# FPGA_Banks_DDR3.net
KiCad netlist of a schematic drawn in Altium Designer
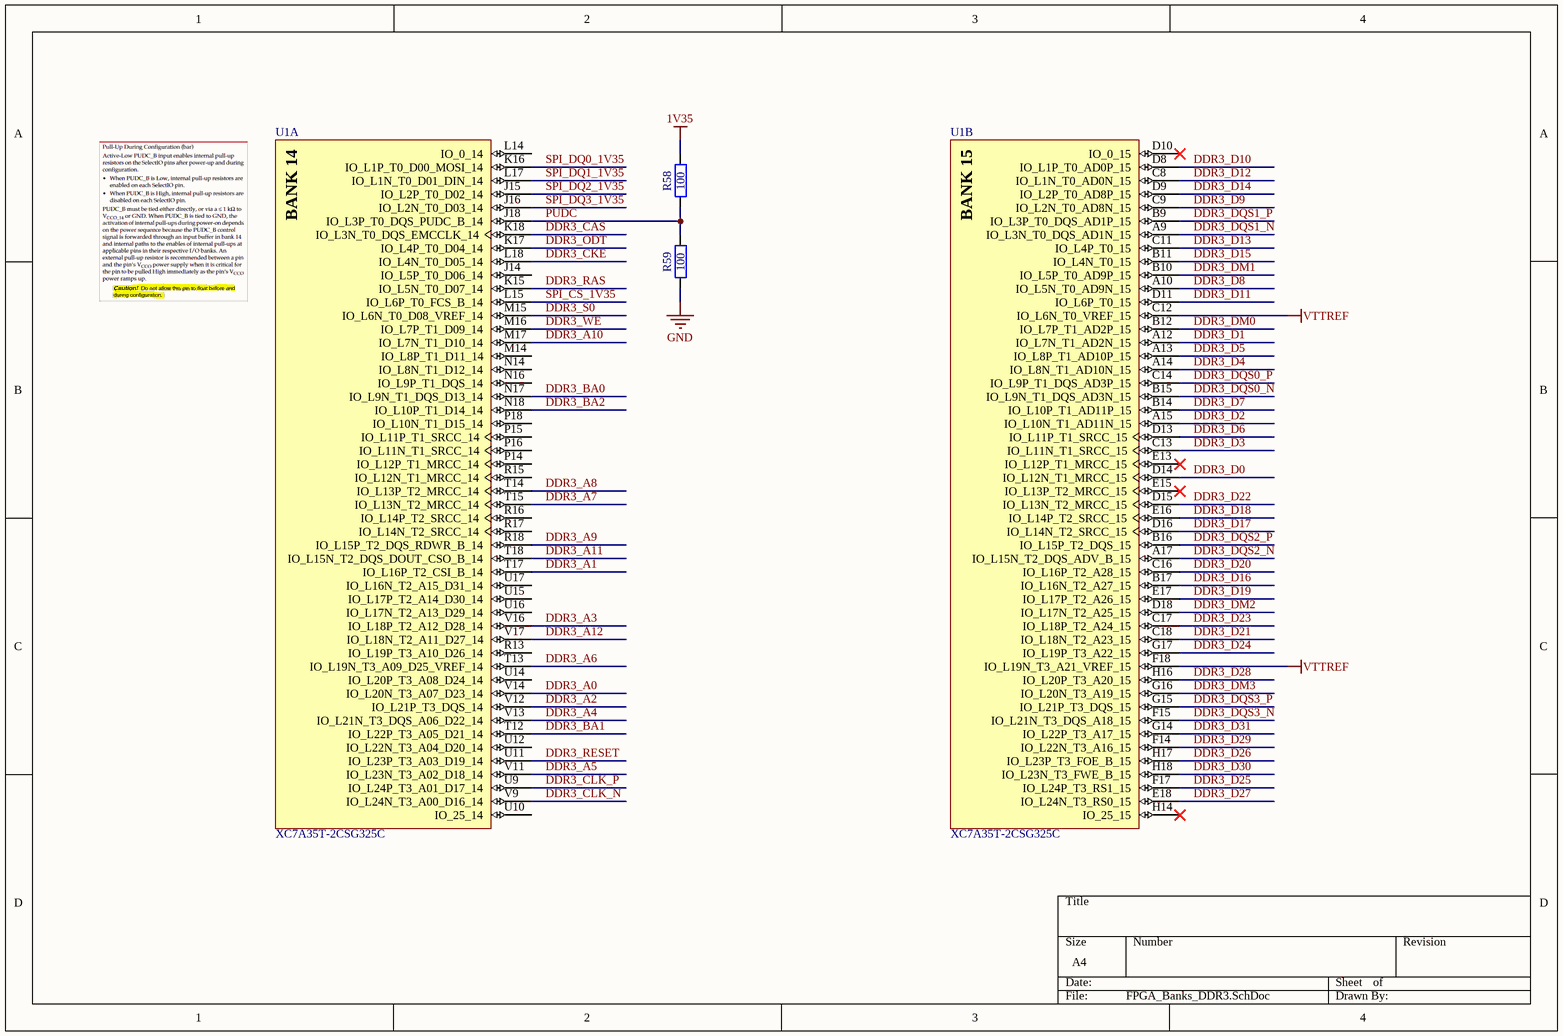
[diagram p0: FPGA_Banks_DDR3.SchDoc]

(export (version "E")
  (design (tool "Eeschema 10.0.6"))
  (components
    (comp (ref "R58")
      (value "100")
      (footprint "GEN_R_0201")
      (fields (field (name "TOLERANCE") "1%"))
      (libsource (lib "DSO") (part "RES 100 OHM 1% 1/20W 0201"))
    )
    (comp (ref "R59")
      (value "100")
      (footprint "GEN_R_0201")
      (fields (field (name "TOLERANCE") "1%"))
      (libsource (lib "DSO") (part "RES 100 OHM 1% 1/20W 0201"))
    )
    (comp (ref "U1")
      (value "XC7A35T-2CSG325C")
      (footprint "CSG325")
      (description "Artix-7 FPGA, 150 User I/Os, 4 GTP, 324-Ball BGA, Speed Grade 2, Commercial Grade, Pb-Free")
      (fields (field (name "MANUFACTURER") "Xilinx"))
      (libsource (lib "Xilinx Artix-7") (part "XC7A35T-2CSG325C"))
    )
  )
  (nets
    (net (code "1") (name "/DDR3_A0") (class "Default")
      (node (ref "U1") (pin "V14") (pinfunction "IO_L20N_T3_A07_D23_14_V14") (pintype "bidirectional"))
    )
    (net (code "2") (name "/DDR3_A1") (class "Default")
      (node (ref "U1") (pin "T17") (pinfunction "IO_L16P_T2_CSI_B_14_T17") (pintype "bidirectional"))
    )
    (net (code "3") (name "/DDR3_A2") (class "Default")
      (node (ref "U1") (pin "V12") (pinfunction "IO_L21P_T3_DQS_14_V12") (pintype "bidirectional"))
    )
    (net (code "4") (name "/DDR3_A3") (class "Default")
      (node (ref "U1") (pin "V16") (pinfunction "IO_L18P_T2_A12_D28_14_V16") (pintype "bidirectional"))
    )
    (net (code "5") (name "/DDR3_A4") (class "Default")
      (node (ref "U1") (pin "V13") (pinfunction "IO_L21N_T3_DQS_A06_D22_14_V13") (pintype "bidirectional"))
    )
    (net (code "6") (name "/DDR3_A5") (class "Default")
      (node (ref "U1") (pin "V11") (pinfunction "IO_L23N_T3_A02_D18_14_V11") (pintype "bidirectional"))
    )
    (net (code "7") (name "/DDR3_A6") (class "Default")
      (node (ref "U1") (pin "T13") (pinfunction "IO_L19N_T3_A09_D25_VREF_14_T13") (pintype "bidirectional"))
    )
    (net (code "8") (name "/DDR3_A7") (class "Default")
      (node (ref "U1") (pin "T15") (pinfunction "IO_L13N_T2_MRCC_14_T15") (pintype "bidirectional"))
    )
    (net (code "9") (name "/DDR3_A8") (class "Default")
      (node (ref "U1") (pin "T14") (pinfunction "IO_L13P_T2_MRCC_14_T14") (pintype "bidirectional"))
    )
    (net (code "10") (name "/DDR3_A9") (class "Default")
      (node (ref "U1") (pin "R18") (pinfunction "IO_L15P_T2_DQS_RDWR_B_14_R18") (pintype "bidirectional"))
    )
    (net (code "11") (name "/DDR3_A10") (class "Default")
      (node (ref "U1") (pin "M17") (pinfunction "IO_L7N_T1_D10_14_M17") (pintype "bidirectional"))
    )
    (net (code "12") (name "/DDR3_A11") (class "Default")
      (node (ref "U1") (pin "T18") (pinfunction "IO_L15N_T2_DQS_DOUT_CSO_B_14_T18") (pintype "bidirectional"))
    )
    (net (code "13") (name "/DDR3_A12") (class "Default")
      (node (ref "U1") (pin "V17") (pinfunction "IO_L18N_T2_A11_D27_14_V17") (pintype "bidirectional"))
    )
    (net (code "14") (name "/DDR3_BA0") (class "Default")
      (node (ref "U1") (pin "N17") (pinfunction "IO_L9N_T1_DQS_D13_14_N17") (pintype "bidirectional"))
    )
    (net (code "15") (name "/DDR3_BA1") (class "Default")
      (node (ref "U1") (pin "T12") (pinfunction "IO_L22P_T3_A05_D21_14_T12") (pintype "bidirectional"))
    )
    (net (code "16") (name "/DDR3_BA2") (class "Default")
      (node (ref "U1") (pin "N18") (pinfunction "IO_L10P_T1_D14_14_N18") (pintype "bidirectional"))
    )
    (net (code "17") (name "/DDR3_CAS") (class "Default")
      (node (ref "U1") (pin "K18") (pinfunction "IO_L3N_T0_DQS_EMCCLK_14_K18") (pintype "bidirectional"))
    )
    (net (code "18") (name "/DDR3_CKE") (class "Default")
      (node (ref "U1") (pin "L18") (pinfunction "IO_L4N_T0_D05_14_L18") (pintype "bidirectional"))
    )
    (net (code "19") (name "/DDR3_CLK_N") (class "Default")
      (node (ref "U1") (pin "V9") (pinfunction "IO_L24N_T3_A00_D16_14_V9") (pintype "bidirectional"))
    )
    (net (code "20") (name "/DDR3_CLK_P") (class "Default")
      (node (ref "U1") (pin "U9") (pinfunction "IO_L24P_T3_A01_D17_14_U9") (pintype "bidirectional"))
    )
    (net (code "21") (name "/DDR3_D0") (class "Default")
      (node (ref "U1") (pin "D14") (pinfunction "IO_L12N_T1_MRCC_15_D14") (pintype "bidirectional"))
    )
    (net (code "22") (name "/DDR3_D1") (class "Default")
      (node (ref "U1") (pin "A12") (pinfunction "IO_L7N_T1_AD2N_15_A12") (pintype "bidirectional"))
    )
    (net (code "23") (name "/DDR3_D2") (class "Default")
      (node (ref "U1") (pin "A15") (pinfunction "IO_L10N_T1_AD11N_15_A15") (pintype "bidirectional"))
    )
    (net (code "24") (name "/DDR3_D3") (class "Default")
      (node (ref "U1") (pin "C13") (pinfunction "IO_L11N_T1_SRCC_15_C13") (pintype "bidirectional"))
    )
    (net (code "25") (name "/DDR3_D4") (class "Default")
      (node (ref "U1") (pin "A14") (pinfunction "IO_L8N_T1_AD10N_15_A14") (pintype "bidirectional"))
    )
    (net (code "26") (name "/DDR3_D5") (class "Default")
      (node (ref "U1") (pin "A13") (pinfunction "IO_L8P_T1_AD10P_15_A13") (pintype "bidirectional"))
    )
    (net (code "27") (name "/DDR3_D6") (class "Default")
      (node (ref "U1") (pin "D13") (pinfunction "IO_L11P_T1_SRCC_15_D13") (pintype "bidirectional"))
    )
    (net (code "28") (name "/DDR3_D7") (class "Default")
      (node (ref "U1") (pin "B14") (pinfunction "IO_L10P_T1_AD11P_15_B14") (pintype "bidirectional"))
    )
    (net (code "29") (name "/DDR3_D8") (class "Default")
      (node (ref "U1") (pin "A10") (pinfunction "IO_L5N_T0_AD9N_15_A10") (pintype "bidirectional"))
    )
    (net (code "30") (name "/DDR3_D9") (class "Default")
      (node (ref "U1") (pin "C9") (pinfunction "IO_L2N_T0_AD8N_15_C9") (pintype "bidirectional"))
    )
    (net (code "31") (name "/DDR3_D10") (class "Default")
      (node (ref "U1") (pin "D8") (pinfunction "IO_L1P_T0_AD0P_15_D8") (pintype "bidirectional"))
    )
    (net (code "32") (name "/DDR3_D11") (class "Default")
      (node (ref "U1") (pin "D11") (pinfunction "IO_L6P_T0_15_D11") (pintype "bidirectional"))
    )
    (net (code "33") (name "/DDR3_D12") (class "Default")
      (node (ref "U1") (pin "C8") (pinfunction "IO_L1N_T0_AD0N_15_C8") (pintype "bidirectional"))
    )
    (net (code "34") (name "/DDR3_D13") (class "Default")
      (node (ref "U1") (pin "C11") (pinfunction "IO_L4P_T0_15_C11") (pintype "bidirectional"))
    )
    (net (code "35") (name "/DDR3_D14") (class "Default")
      (node (ref "U1") (pin "D9") (pinfunction "IO_L2P_T0_AD8P_15_D9") (pintype "bidirectional"))
    )
    (net (code "36") (name "/DDR3_D15") (class "Default")
      (node (ref "U1") (pin "B11") (pinfunction "IO_L4N_T0_15_B11") (pintype "bidirectional"))
    )
    (net (code "37") (name "/DDR3_D16") (class "Default")
      (node (ref "U1") (pin "B17") (pinfunction "IO_L16N_T2_A27_15_B17") (pintype "bidirectional"))
    )
    (net (code "38") (name "/DDR3_D17") (class "Default")
      (node (ref "U1") (pin "D16") (pinfunction "IO_L14N_T2_SRCC_15_D16") (pintype "bidirectional"))
    )
    (net (code "39") (name "/DDR3_D18") (class "Default")
      (node (ref "U1") (pin "E16") (pinfunction "IO_L14P_T2_SRCC_15_E16") (pintype "bidirectional"))
    )
    (net (code "40") (name "/DDR3_D19") (class "Default")
      (node (ref "U1") (pin "E17") (pinfunction "IO_L17P_T2_A26_15_E17") (pintype "bidirectional"))
    )
    (net (code "41") (name "/DDR3_D20") (class "Default")
      (node (ref "U1") (pin "C16") (pinfunction "IO_L16P_T2_A28_15_C16") (pintype "bidirectional"))
    )
    (net (code "42") (name "/DDR3_D21") (class "Default")
      (node (ref "U1") (pin "C18") (pinfunction "IO_L18N_T2_A23_15_C18") (pintype "bidirectional"))
    )
    (net (code "43") (name "/DDR3_D22") (class "Default")
      (node (ref "U1") (pin "D15") (pinfunction "IO_L13N_T2_MRCC_15_D15") (pintype "bidirectional"))
    )
    (net (code "44") (name "/DDR3_D23") (class "Default")
      (node (ref "U1") (pin "C17") (pinfunction "IO_L18P_T2_A24_15_C17") (pintype "bidirectional"))
    )
    (net (code "45") (name "/DDR3_D24") (class "Default")
      (node (ref "U1") (pin "G17") (pinfunction "IO_L19P_T3_A22_15_G17") (pintype "bidirectional"))
    )
    (net (code "46") (name "/DDR3_D25") (class "Default")
      (node (ref "U1") (pin "F17") (pinfunction "IO_L24P_T3_RS1_15_F17") (pintype "bidirectional"))
    )
    (net (code "47") (name "/DDR3_D26") (class "Default")
      (node (ref "U1") (pin "H17") (pinfunction "IO_L23P_T3_FOE_B_15_H17") (pintype "bidirectional"))
    )
    (net (code "48") (name "/DDR3_D27") (class "Default")
      (node (ref "U1") (pin "E18") (pinfunction "IO_L24N_T3_RS0_15_E18") (pintype "bidirectional"))
    )
    (net (code "49") (name "/DDR3_D28") (class "Default")
      (node (ref "U1") (pin "H16") (pinfunction "IO_L20P_T3_A20_15_H16") (pintype "bidirectional"))
    )
    (net (code "50") (name "/DDR3_D29") (class "Default")
      (node (ref "U1") (pin "F14") (pinfunction "IO_L22N_T3_A16_15_F14") (pintype "bidirectional"))
    )
    (net (code "51") (name "/DDR3_D30") (class "Default")
      (node (ref "U1") (pin "H18") (pinfunction "IO_L23N_T3_FWE_B_15_H18") (pintype "bidirectional"))
    )
    (net (code "52") (name "/DDR3_D31") (class "Default")
      (node (ref "U1") (pin "G14") (pinfunction "IO_L22P_T3_A17_15_G14") (pintype "bidirectional"))
    )
    (net (code "53") (name "/DDR3_DM0") (class "Default")
      (node (ref "U1") (pin "B12") (pinfunction "IO_L7P_T1_AD2P_15_B12") (pintype "bidirectional"))
    )
    (net (code "54") (name "/DDR3_DM1") (class "Default")
      (node (ref "U1") (pin "B10") (pinfunction "IO_L5P_T0_AD9P_15_B10") (pintype "bidirectional"))
    )
    (net (code "55") (name "/DDR3_DM2") (class "Default")
      (node (ref "U1") (pin "D18") (pinfunction "IO_L17N_T2_A25_15_D18") (pintype "bidirectional"))
    )
    (net (code "56") (name "/DDR3_DM3") (class "Default")
      (node (ref "U1") (pin "G16") (pinfunction "IO_L20N_T3_A19_15_G16") (pintype "bidirectional"))
    )
    (net (code "57") (name "/DDR3_DQS0_N") (class "Default")
      (node (ref "U1") (pin "B15") (pinfunction "IO_L9N_T1_DQS_AD3N_15_B15") (pintype "bidirectional"))
    )
    (net (code "58") (name "/DDR3_DQS0_P") (class "Default")
      (node (ref "U1") (pin "C14") (pinfunction "IO_L9P_T1_DQS_AD3P_15_C14") (pintype "bidirectional"))
    )
    (net (code "59") (name "/DDR3_DQS1_N") (class "Default")
      (node (ref "U1") (pin "A9") (pinfunction "IO_L3N_T0_DQS_AD1N_15_A9") (pintype "bidirectional"))
    )
    (net (code "60") (name "/DDR3_DQS1_P") (class "Default")
      (node (ref "U1") (pin "B9") (pinfunction "IO_L3P_T0_DQS_AD1P_15_B9") (pintype "bidirectional"))
    )
    (net (code "61") (name "/DDR3_DQS2_N") (class "Default")
      (node (ref "U1") (pin "A17") (pinfunction "IO_L15N_T2_DQS_ADV_B_15_A17") (pintype "bidirectional"))
    )
    (net (code "62") (name "/DDR3_DQS2_P") (class "Default")
      (node (ref "U1") (pin "B16") (pinfunction "IO_L15P_T2_DQS_15_B16") (pintype "bidirectional"))
    )
    (net (code "63") (name "/DDR3_DQS3_N") (class "Default")
      (node (ref "U1") (pin "F15") (pinfunction "IO_L21N_T3_DQS_A18_15_F15") (pintype "bidirectional"))
    )
    (net (code "64") (name "/DDR3_DQS3_P") (class "Default")
      (node (ref "U1") (pin "G15") (pinfunction "IO_L21P_T3_DQS_15_G15") (pintype "bidirectional"))
    )
    (net (code "65") (name "/DDR3_ODT") (class "Default")
      (node (ref "U1") (pin "K17") (pinfunction "IO_L4P_T0_D04_14_K17") (pintype "bidirectional"))
    )
    (net (code "66") (name "/DDR3_RAS") (class "Default")
      (node (ref "U1") (pin "K15") (pinfunction "IO_L5N_T0_D07_14_K15") (pintype "bidirectional"))
    )
    (net (code "67") (name "/DDR3_RESET") (class "Default")
      (node (ref "U1") (pin "U11") (pinfunction "IO_L23P_T3_A03_D19_14_U11") (pintype "bidirectional"))
    )
    (net (code "68") (name "/DDR3_S0") (class "Default")
      (node (ref "U1") (pin "M15") (pinfunction "IO_L6N_T0_D08_VREF_14_M15") (pintype "bidirectional"))
    )
    (net (code "69") (name "/DDR3_WE") (class "Default")
      (node (ref "U1") (pin "M16") (pinfunction "IO_L7P_T1_D09_14_M16") (pintype "bidirectional"))
    )
    (net (code "70") (name "/PUDC") (class "Default")
      (node (ref "R58") (pin "1") (pinfunction "1_1") (pintype "passive"))
      (node (ref "R59") (pin "2") (pinfunction "2_2") (pintype "passive"))
      (node (ref "U1") (pin "J18") (pinfunction "IO_L3P_T0_DQS_PUDC_B_14_J18") (pintype "bidirectional"))
    )
    (net (code "71") (name "/SPI_CS_1V35") (class "Default")
      (node (ref "U1") (pin "L15") (pinfunction "IO_L6P_T0_FCS_B_14_L15") (pintype "bidirectional"))
    )
    (net (code "72") (name "/SPI_DQ0_1V35") (class "Default")
      (node (ref "U1") (pin "K16") (pinfunction "IO_L1P_T0_D00_MOSI_14_K16") (pintype "bidirectional"))
    )
    (net (code "73") (name "/SPI_DQ1_1V35") (class "Default")
      (node (ref "U1") (pin "L17") (pinfunction "IO_L1N_T0_D01_DIN_14_L17") (pintype "bidirectional"))
    )
    (net (code "74") (name "/SPI_DQ2_1V35") (class "Default")
      (node (ref "U1") (pin "J15") (pinfunction "IO_L2P_T0_D02_14_J15") (pintype "bidirectional"))
    )
    (net (code "75") (name "/SPI_DQ3_1V35") (class "Default")
      (node (ref "U1") (pin "J16") (pinfunction "IO_L2N_T0_D03_14_J16") (pintype "bidirectional"))
    )
    (net (code "76") (name "1V35") (class "Default")
      (node (ref "R58") (pin "2") (pinfunction "2_2") (pintype "passive"))
    )
    (net (code "77") (name "GND") (class "Default")
      (node (ref "R59") (pin "1") (pinfunction "1_1") (pintype "passive"))
    )
    (net (code "78") (name "VTTREF") (class "Default")
      (node (ref "U1") (pin "C12") (pinfunction "IO_L6N_T0_VREF_15_C12") (pintype "bidirectional"))
      (node (ref "U1") (pin "F18") (pinfunction "IO_L19N_T3_A21_VREF_15_F18") (pintype "bidirectional"))
    )
    (net (code "79") (name "unconnected-(U1A-IO_0_14-PadL14)") (class "Default")
      (node (ref "U1") (pin "L14") (pinfunction "IO_0_14_L14") (pintype "bidirectional"))
    )
    (net (code "80") (name "unconnected-(U1A-IO_25_14-PadU10)") (class "Default")
      (node (ref "U1") (pin "U10") (pinfunction "IO_25_14_U10") (pintype "bidirectional"))
    )
    (net (code "81") (name "unconnected-(U1A-IO_L5P_T0_D06_14-PadJ14)") (class "Default")
      (node (ref "U1") (pin "J14") (pinfunction "IO_L5P_T0_D06_14_J14") (pintype "bidirectional"))
    )
    (net (code "82") (name "unconnected-(U1A-IO_L8N_T1_D12_14-PadN14)") (class "Default")
      (node (ref "U1") (pin "N14") (pinfunction "IO_L8N_T1_D12_14_N14") (pintype "bidirectional"))
    )
    (net (code "83") (name "unconnected-(U1A-IO_L8P_T1_D11_14-PadM14)") (class "Default")
      (node (ref "U1") (pin "M14") (pinfunction "IO_L8P_T1_D11_14_M14") (pintype "bidirectional"))
    )
    (net (code "84") (name "unconnected-(U1A-IO_L9P_T1_DQS_14-PadN16)") (class "Default")
      (node (ref "U1") (pin "N16") (pinfunction "IO_L9P_T1_DQS_14_N16") (pintype "bidirectional"))
    )
    (net (code "85") (name "unconnected-(U1A-IO_L10N_T1_D15_14-PadP18)") (class "Default")
      (node (ref "U1") (pin "P18") (pinfunction "IO_L10N_T1_D15_14_P18") (pintype "bidirectional"))
    )
    (net (code "86") (name "unconnected-(U1A-IO_L11N_T1_SRCC_14-PadP16)") (class "Default")
      (node (ref "U1") (pin "P16") (pinfunction "IO_L11N_T1_SRCC_14_P16") (pintype "bidirectional"))
    )
    (net (code "87") (name "unconnected-(U1A-IO_L11P_T1_SRCC_14-PadP15)") (class "Default")
      (node (ref "U1") (pin "P15") (pinfunction "IO_L11P_T1_SRCC_14_P15") (pintype "bidirectional"))
    )
    (net (code "88") (name "unconnected-(U1A-IO_L12N_T1_MRCC_14-PadR15)") (class "Default")
      (node (ref "U1") (pin "R15") (pinfunction "IO_L12N_T1_MRCC_14_R15") (pintype "bidirectional"))
    )
    (net (code "89") (name "unconnected-(U1A-IO_L12P_T1_MRCC_14-PadP14)") (class "Default")
      (node (ref "U1") (pin "P14") (pinfunction "IO_L12P_T1_MRCC_14_P14") (pintype "bidirectional"))
    )
    (net (code "90") (name "unconnected-(U1A-IO_L14N_T2_SRCC_14-PadR17)") (class "Default")
      (node (ref "U1") (pin "R17") (pinfunction "IO_L14N_T2_SRCC_14_R17") (pintype "bidirectional"))
    )
    (net (code "91") (name "unconnected-(U1A-IO_L14P_T2_SRCC_14-PadR16)") (class "Default")
      (node (ref "U1") (pin "R16") (pinfunction "IO_L14P_T2_SRCC_14_R16") (pintype "bidirectional"))
    )
    (net (code "92") (name "unconnected-(U1A-IO_L16N_T2_A15_D31_14-PadU17)") (class "Default")
      (node (ref "U1") (pin "U17") (pinfunction "IO_L16N_T2_A15_D31_14_U17") (pintype "bidirectional"))
    )
    (net (code "93") (name "unconnected-(U1A-IO_L17N_T2_A13_D29_14-PadU16)") (class "Default")
      (node (ref "U1") (pin "U16") (pinfunction "IO_L17N_T2_A13_D29_14_U16") (pintype "bidirectional"))
    )
    (net (code "94") (name "unconnected-(U1A-IO_L17P_T2_A14_D30_14-PadU15)") (class "Default")
      (node (ref "U1") (pin "U15") (pinfunction "IO_L17P_T2_A14_D30_14_U15") (pintype "bidirectional"))
    )
    (net (code "95") (name "unconnected-(U1A-IO_L19P_T3_A10_D26_14-PadR13)") (class "Default")
      (node (ref "U1") (pin "R13") (pinfunction "IO_L19P_T3_A10_D26_14_R13") (pintype "bidirectional"))
    )
    (net (code "96") (name "unconnected-(U1A-IO_L20P_T3_A08_D24_14-PadU14)") (class "Default")
      (node (ref "U1") (pin "U14") (pinfunction "IO_L20P_T3_A08_D24_14_U14") (pintype "bidirectional"))
    )
    (net (code "97") (name "unconnected-(U1A-IO_L22N_T3_A04_D20_14-PadU12)") (class "Default")
      (node (ref "U1") (pin "U12") (pinfunction "IO_L22N_T3_A04_D20_14_U12") (pintype "bidirectional"))
    )
    (net (code "98") (name "unconnected-(U1B-IO_0_15-PadD10)") (class "Default")
      (node (ref "U1") (pin "D10") (pinfunction "IO_0_15_D10") (pintype "bidirectional+no_connect"))
    )
    (net (code "99") (name "unconnected-(U1B-IO_25_15-PadH14)") (class "Default")
      (node (ref "U1") (pin "H14") (pinfunction "IO_25_15_H14") (pintype "bidirectional+no_connect"))
    )
    (net (code "100") (name "unconnected-(U1B-IO_L12P_T1_MRCC_15-PadE13)") (class "Default")
      (node (ref "U1") (pin "E13") (pinfunction "IO_L12P_T1_MRCC_15_E13") (pintype "bidirectional+no_connect"))
    )
    (net (code "101") (name "unconnected-(U1B-IO_L13P_T2_MRCC_15-PadE15)") (class "Default")
      (node (ref "U1") (pin "E15") (pinfunction "IO_L13P_T2_MRCC_15_E15") (pintype "bidirectional+no_connect"))
    )
  )
)
